# CDRon_mainSheet.net
KiCad netlist of a schematic drawn in Altium Designer
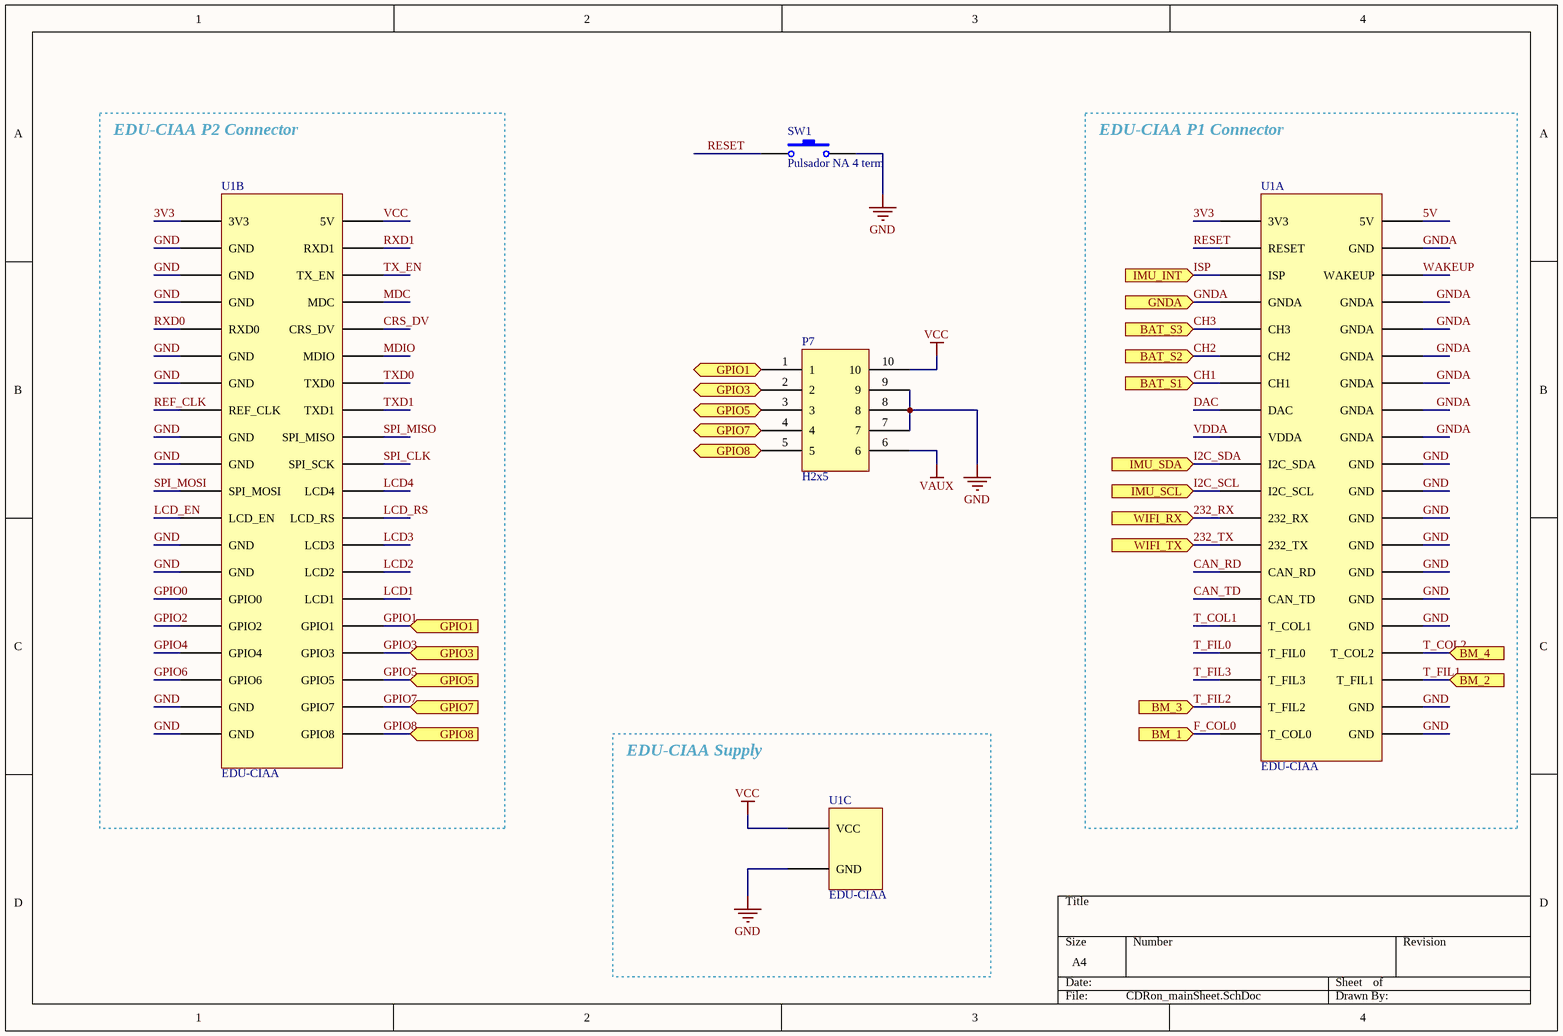
[diagram p0: CDRon_mainSheet.SchDoc]

(export (version "E")
  (design (tool "Eeschema 10.0.6"))
  (components
    (comp (ref "P7") (value "H2x5") (footprint "H2x5") (libsource (lib "CDRon_lib") (part "H2x5")))
    (comp (ref "SW1")
      (value "Pulsador NA 4 term")
      (footprint "TACT SW")
      (fields (field (name ".CREATOR") "G") (field (name ".PCBCHECK") "G") (field (name ".SCHCHECK") "G"))
      (libsource (lib "CDRon_lib") (part "Pulsador NA 4 term"))
    )
    (comp (ref "U1")
      (value "EDU-CIAA")
      (footprint "EDU-CIAA")
      (libsource (lib "CDRon_lib") (part "EDU-CIAA"))
    )
  )
  (nets
    (net (code "1") (name "/3V3") (class "Default")
      (node (ref "U1") (pin "1") (pinfunction "3V3_1") (pintype "passive"))
      (node (ref "U1") (pin "41") (pinfunction "3V3_41") (pintype "passive"))
    )
    (net (code "2") (name "/5V") (class "Default")
      (node (ref "U1") (pin "2") (pinfunction "5V_2") (pintype "passive"))
    )
    (net (code "3") (name "/232_RX") (class "Default")
      (node (ref "U1") (pin "23") (pinfunction "232_RX_23") (pintype "passive"))
    )
    (net (code "4") (name "/232_TX") (class "Default")
      (node (ref "U1") (pin "25") (pinfunction "232_TX_25") (pintype "passive"))
    )
    (net (code "5") (name "/CAN_RD") (class "Default")
      (node (ref "U1") (pin "27") (pinfunction "CAN_RD_27") (pintype "passive"))
    )
    (net (code "6") (name "/CAN_TD") (class "Default")
      (node (ref "U1") (pin "29") (pinfunction "CAN_TD_29") (pintype "passive"))
    )
    (net (code "7") (name "/CH1") (class "Default")
      (node (ref "U1") (pin "13") (pinfunction "CH1_13") (pintype "passive"))
    )
    (net (code "8") (name "/CH2") (class "Default")
      (node (ref "U1") (pin "11") (pinfunction "CH2_11") (pintype "passive"))
    )
    (net (code "9") (name "/CH3") (class "Default")
      (node (ref "U1") (pin "9") (pinfunction "CH3_9") (pintype "passive"))
    )
    (net (code "10") (name "/CRS_DV") (class "Default")
      (node (ref "U1") (pin "50") (pinfunction "CRS_DV_50") (pintype "passive"))
    )
    (net (code "11") (name "/DAC") (class "Default")
      (node (ref "U1") (pin "15") (pinfunction "DAC_15") (pintype "passive"))
    )
    (net (code "12") (name "/F_COL0") (class "Default")
      (node (ref "U1") (pin "39") (pinfunction "T_COL0_39") (pintype "passive"))
    )
    (net (code "13") (name "/GNDA") (class "Default")
      (node (ref "U1") (pin "10") (pinfunction "GNDA_10") (pintype "passive"))
      (node (ref "U1") (pin "12") (pinfunction "GNDA_12") (pintype "passive"))
      (node (ref "U1") (pin "14") (pinfunction "GNDA_14") (pintype "passive"))
      (node (ref "U1") (pin "16") (pinfunction "GNDA_16") (pintype "passive"))
      (node (ref "U1") (pin "18") (pinfunction "GNDA_18") (pintype "passive"))
      (node (ref "U1") (pin "4") (pinfunction "GND_4") (pintype "passive"))
      (node (ref "U1") (pin "7") (pinfunction "GNDA_7") (pintype "passive"))
      (node (ref "U1") (pin "8") (pinfunction "GNDA_8") (pintype "passive"))
    )
    (net (code "14") (name "/GPIO0") (class "Default")
      (node (ref "U1") (pin "69") (pinfunction "GPIO0_69") (pintype "passive"))
    )
    (net (code "15") (name "/GPIO1") (class "Default")
      (node (ref "P7") (pin "1") (pinfunction "1_1") (pintype "passive"))
      (node (ref "U1") (pin "72") (pinfunction "GPIO1_72") (pintype "passive"))
    )
    (net (code "16") (name "/GPIO2") (class "Default")
      (node (ref "U1") (pin "71") (pinfunction "GPIO2_71") (pintype "passive"))
    )
    (net (code "17") (name "/GPIO3") (class "Default")
      (node (ref "P7") (pin "2") (pinfunction "2_2") (pintype "passive"))
      (node (ref "U1") (pin "74") (pinfunction "GPIO3_74") (pintype "passive"))
    )
    (net (code "18") (name "/GPIO4") (class "Default")
      (node (ref "U1") (pin "73") (pinfunction "GPIO4_73") (pintype "passive"))
    )
    (net (code "19") (name "/GPIO5") (class "Default")
      (node (ref "P7") (pin "3") (pinfunction "3_3") (pintype "passive"))
      (node (ref "U1") (pin "76") (pinfunction "GPIO5_76") (pintype "passive"))
    )
    (net (code "20") (name "/GPIO6") (class "Default")
      (node (ref "U1") (pin "75") (pinfunction "GPIO6_75") (pintype "passive"))
    )
    (net (code "21") (name "/GPIO7") (class "Default")
      (node (ref "P7") (pin "4") (pinfunction "4_4") (pintype "passive"))
      (node (ref "U1") (pin "78") (pinfunction "GPIO7_78") (pintype "passive"))
    )
    (net (code "22") (name "/GPIO8") (class "Default")
      (node (ref "P7") (pin "5") (pinfunction "5_5") (pintype "passive"))
      (node (ref "U1") (pin "80") (pinfunction "GPIO8_80") (pintype "passive"))
    )
    (net (code "23") (name "/I2C_SCL") (class "Default")
      (node (ref "U1") (pin "21") (pinfunction "I2C_SCL_21") (pintype "passive"))
    )
    (net (code "24") (name "/I2C_SDA") (class "Default")
      (node (ref "U1") (pin "19") (pinfunction "I2C_SDA_19") (pintype "passive"))
    )
    (net (code "25") (name "/ISP") (class "Default")
      (node (ref "U1") (pin "5") (pinfunction "ISP_5") (pintype "passive"))
    )
    (net (code "26") (name "/LCD1") (class "Default")
      (node (ref "U1") (pin "70") (pinfunction "LCD1_70") (pintype "passive"))
    )
    (net (code "27") (name "/LCD2") (class "Default")
      (node (ref "U1") (pin "68") (pinfunction "LCD2_68") (pintype "passive"))
    )
    (net (code "28") (name "/LCD3") (class "Default")
      (node (ref "U1") (pin "66") (pinfunction "LCD3_66") (pintype "passive"))
    )
    (net (code "29") (name "/LCD4") (class "Default")
      (node (ref "U1") (pin "62") (pinfunction "LCD4_62") (pintype "passive"))
    )
    (net (code "30") (name "/LCD_EN") (class "Default")
      (node (ref "U1") (pin "63") (pinfunction "LCD_EN_63") (pintype "passive"))
    )
    (net (code "31") (name "/LCD_RS") (class "Default")
      (node (ref "U1") (pin "64") (pinfunction "LCD_RS_64") (pintype "passive"))
    )
    (net (code "32") (name "/MDC") (class "Default")
      (node (ref "U1") (pin "48") (pinfunction "MDC_48") (pintype "passive"))
    )
    (net (code "33") (name "/MDIO") (class "Default")
      (node (ref "U1") (pin "52") (pinfunction "MDIO_52") (pintype "passive"))
    )
    (net (code "34") (name "/REF_CLK") (class "Default")
      (node (ref "U1") (pin "55") (pinfunction "REF_CLK_55") (pintype "passive"))
    )
    (net (code "35") (name "/RESET") (class "Default")
      (node (ref "SW1") (pin "1") (pinfunction "1_1") (pintype "passive"))
      (node (ref "U1") (pin "3") (pinfunction "RESET_3") (pintype "passive"))
    )
    (net (code "36") (name "/RXD0") (class "Default")
      (node (ref "U1") (pin "49") (pinfunction "RXD0_49") (pintype "passive"))
    )
    (net (code "37") (name "/RXD1") (class "Default")
      (node (ref "U1") (pin "44") (pinfunction "RXD1_44") (pintype "passive"))
    )
    (net (code "38") (name "/SPI_CLK") (class "Default")
      (node (ref "U1") (pin "60") (pinfunction "SPI_SCK_60") (pintype "passive"))
    )
    (net (code "39") (name "/SPI_MISO") (class "Default")
      (node (ref "U1") (pin "58") (pinfunction "SPI_MISO_58") (pintype "passive"))
    )
    (net (code "40") (name "/SPI_MOSI") (class "Default")
      (node (ref "U1") (pin "61") (pinfunction "SPI_MOSI_61") (pintype "passive"))
    )
    (net (code "41") (name "/TXD0") (class "Default")
      (node (ref "U1") (pin "54") (pinfunction "TXD0_54") (pintype "passive"))
    )
    (net (code "42") (name "/TXD1") (class "Default")
      (node (ref "U1") (pin "56") (pinfunction "TXD1_56") (pintype "passive"))
    )
    (net (code "43") (name "/TX_EN") (class "Default")
      (node (ref "U1") (pin "46") (pinfunction "TX_EN_46") (pintype "passive"))
    )
    (net (code "44") (name "/T_COL1") (class "Default")
      (node (ref "U1") (pin "31") (pinfunction "T_COL1_31") (pintype "passive"))
    )
    (net (code "45") (name "/T_COL2") (class "Default")
      (node (ref "U1") (pin "34") (pinfunction "T_COL2_34") (pintype "passive"))
    )
    (net (code "46") (name "/T_FIL0") (class "Default")
      (node (ref "U1") (pin "33") (pinfunction "T_FIL0_33") (pintype "passive"))
    )
    (net (code "47") (name "/T_FIL1") (class "Default")
      (node (ref "U1") (pin "36") (pinfunction "T_FIL1_36") (pintype "passive"))
    )
    (net (code "48") (name "/T_FIL2") (class "Default")
      (node (ref "U1") (pin "37") (pinfunction "T_FIL2_37") (pintype "passive"))
    )
    (net (code "49") (name "/T_FIL3") (class "Default")
      (node (ref "U1") (pin "35") (pinfunction "T_FIL3_35") (pintype "passive"))
    )
    (net (code "50") (name "/VDDA") (class "Default")
      (node (ref "U1") (pin "17") (pinfunction "VDDA_17") (pintype "passive"))
    )
    (net (code "51") (name "/WAKEUP") (class "Default")
      (node (ref "U1") (pin "6") (pinfunction "WAKEUP_6") (pintype "passive"))
    )
    (net (code "52") (name "GND") (class "Default")
      (node (ref "P7") (pin "7") (pinfunction "7_7") (pintype "passive"))
      (node (ref "P7") (pin "8") (pinfunction "8_8") (pintype "passive"))
      (node (ref "P7") (pin "9") (pinfunction "9_9") (pintype "passive"))
      (node (ref "SW1") (pin "2") (pinfunction "2_2") (pintype "passive"))
      (node (ref "U1") (pin "20") (pinfunction "GND_20") (pintype "passive"))
      (node (ref "U1") (pin "22") (pinfunction "GND_22") (pintype "passive"))
      (node (ref "U1") (pin "24") (pinfunction "GND_24") (pintype "passive"))
      (node (ref "U1") (pin "26") (pinfunction "GND_26") (pintype "passive"))
      (node (ref "U1") (pin "28") (pinfunction "GND_28") (pintype "passive"))
      (node (ref "U1") (pin "30") (pinfunction "GND_30") (pintype "passive"))
      (node (ref "U1") (pin "32") (pinfunction "GND_32") (pintype "passive"))
      (node (ref "U1") (pin "38") (pinfunction "GND_38") (pintype "passive"))
      (node (ref "U1") (pin "40") (pinfunction "GND_40") (pintype "passive"))
      (node (ref "U1") (pin "43") (pinfunction "GND_43") (pintype "passive"))
      (node (ref "U1") (pin "45") (pinfunction "GND_45") (pintype "passive"))
      (node (ref "U1") (pin "47") (pinfunction "GND_47") (pintype "passive"))
      (node (ref "U1") (pin "51") (pinfunction "GND_51") (pintype "passive"))
      (node (ref "U1") (pin "53") (pinfunction "GND_53") (pintype "passive"))
      (node (ref "U1") (pin "57") (pinfunction "GND_57") (pintype "passive"))
      (node (ref "U1") (pin "59") (pinfunction "GND_59") (pintype "passive"))
      (node (ref "U1") (pin "65") (pinfunction "GND_65") (pintype "passive"))
      (node (ref "U1") (pin "67") (pinfunction "GND_67") (pintype "passive"))
      (node (ref "U1") (pin "77") (pinfunction "GND_77") (pintype "passive"))
      (node (ref "U1") (pin "79") (pinfunction "GND_79") (pintype "passive"))
      (node (ref "U1") (pin "82") (pinfunction "GND_82") (pintype "passive"))
    )
    (net (code "53") (name "VAUX") (class "Default")
      (node (ref "P7") (pin "6") (pinfunction "6_6") (pintype "passive"))
    )
    (net (code "54") (name "VCC") (class "Default")
      (node (ref "P7") (pin "10") (pinfunction "10_10") (pintype "passive"))
      (node (ref "U1") (pin "42") (pinfunction "5V_42") (pintype "passive"))
      (node (ref "U1") (pin "81") (pinfunction "VCC_81") (pintype "passive"))
    )
  )
)
